# TerminalShield.net
KiCad netlist of a schematic drawn in EAGLE
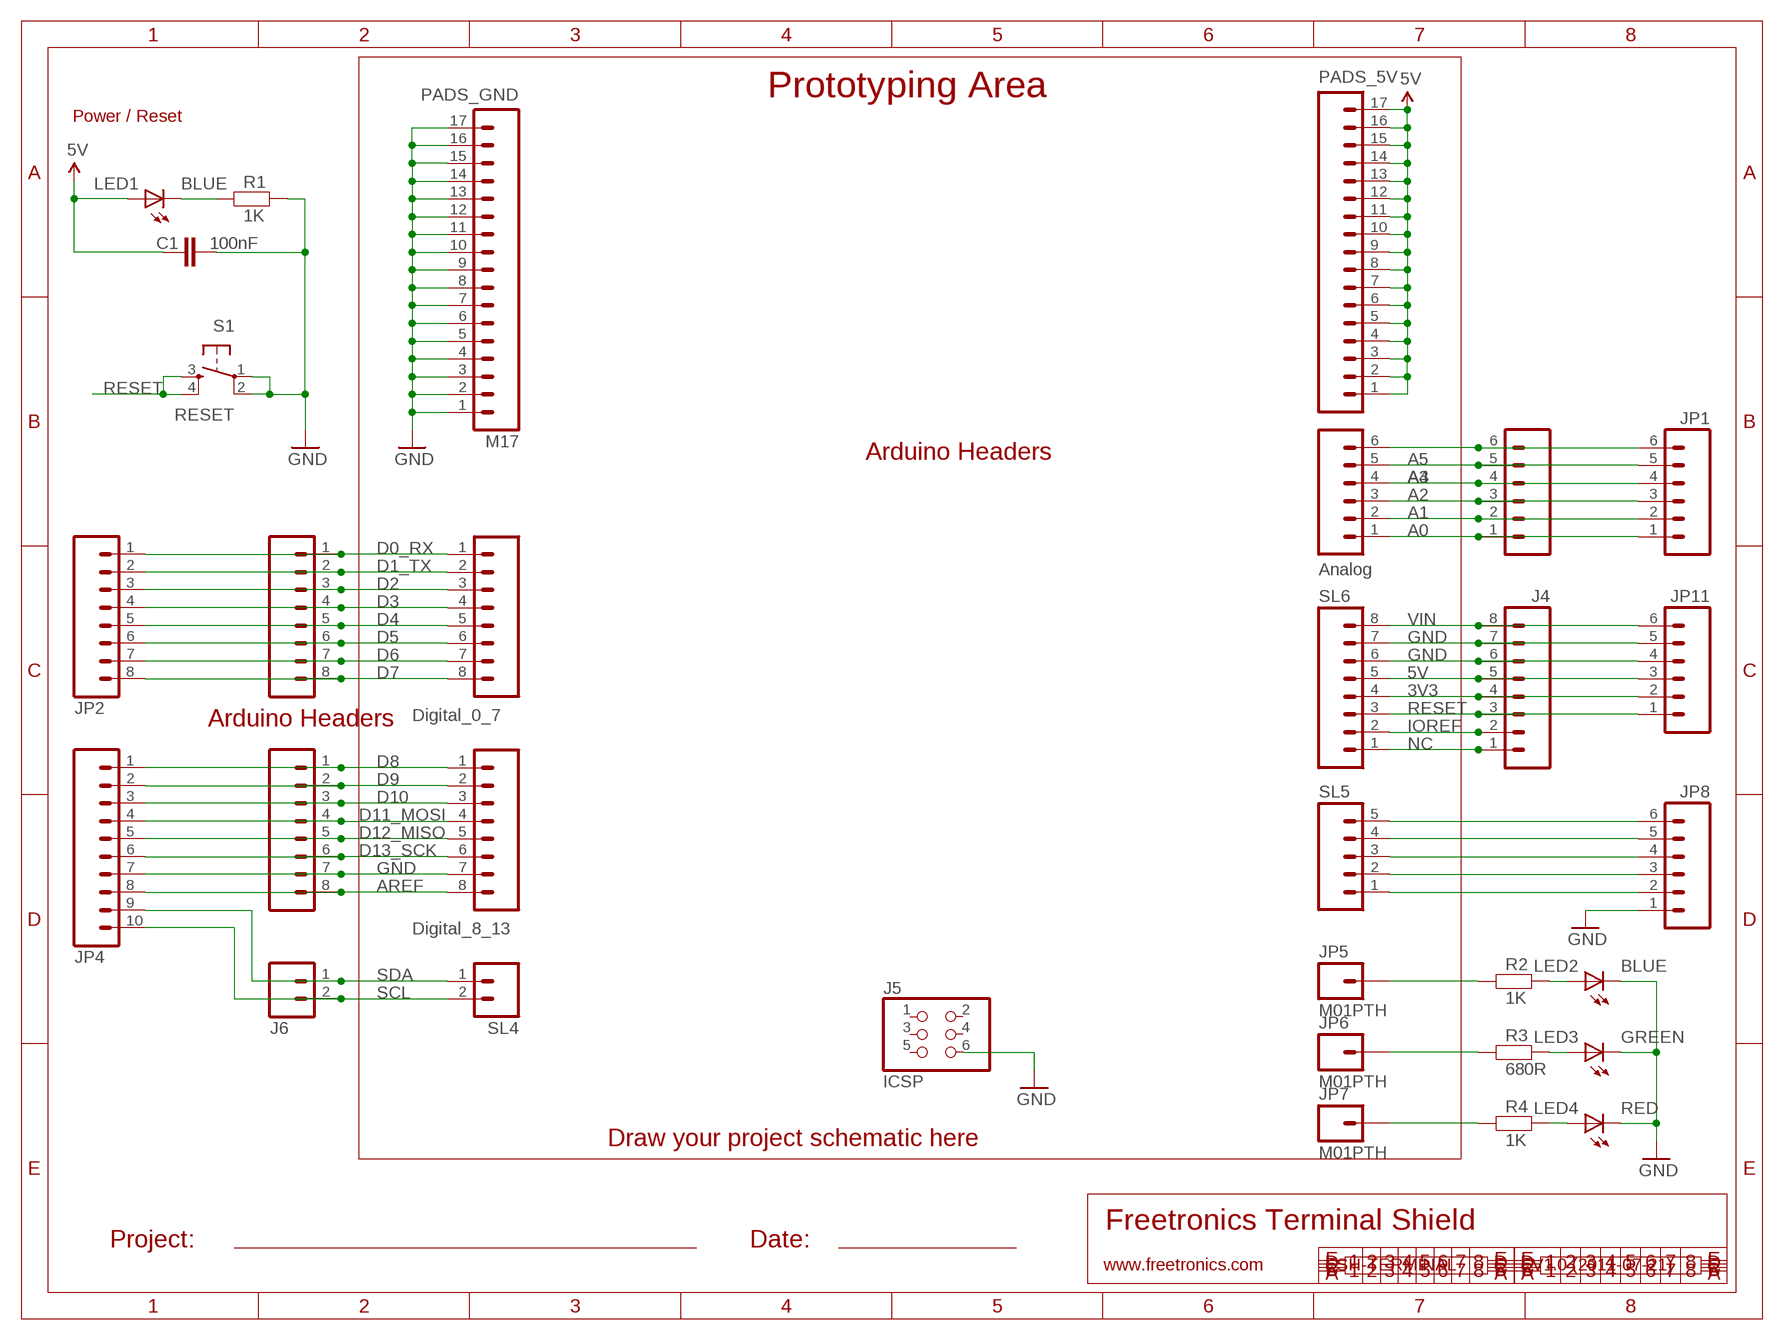
[diagram p0: schematic, sheet 1]

(export (version "E")
  (design (tool "Eeschema 10.0.6"))
  (components
    (comp (ref "C1")
      (value "100nF")
      (footprint "eagle-import:0603")
      (libsource (lib "eagle-import") (part "CAP0603"))
    )
    (comp (ref "J1")
      (value "Analog")
      (footprint "eagle-import:1X06")
      (libsource (lib "eagle-import") (part "M06SIP"))
    )
    (comp (ref "J2")
      (value "Digital_0_7")
      (footprint "eagle-import:1X08")
      (libsource (lib "eagle-import") (part "M08"))
    )
    (comp (ref "J3")
      (value "Digital_8_13")
      (footprint "eagle-import:1X08")
      (libsource (lib "eagle-import") (part "M08"))
    )
    (comp (ref "J4")
      (value "M08STD")
      (footprint "eagle-import:1X08")
      (libsource (lib "eagle-import") (part "M08STD"))
    )
    (comp (ref "J5")
      (value "ICSP")
      (footprint "eagle-import:2X03")
      (libsource (lib "eagle-import") (part "PINHD-2X3"))
    )
    (comp (ref "J6")
      (value "M02PTH")
      (footprint "eagle-import:1X02")
      (libsource (lib "eagle-import") (part "M02PTH"))
    )
    (comp (ref "JP1")
      (value "M06")
      (footprint "eagle-import:TERMINALBLOCK_3.5MM_6")
      (libsource (lib "eagle-import") (part "freetronics-master-v1_M06"))
    )
    (comp (ref "JP2")
      (value "M08")
      (footprint "eagle-import:TERMINALBLOCK_3.5MM_8")
      (libsource (lib "eagle-import") (part "freetronics-master-v1_M08"))
    )
    (comp (ref "JP4")
      (value "M10")
      (footprint "eagle-import:TERMINALBLOCK_3.5MM_10")
      (libsource (lib "eagle-import") (part "M10"))
    )
    (comp (ref "JP5")
      (value "M01PTH")
      (footprint "eagle-import:1X01")
      (libsource (lib "eagle-import") (part "M01PTH"))
    )
    (comp (ref "JP6")
      (value "M01PTH")
      (footprint "eagle-import:1X01")
      (libsource (lib "eagle-import") (part "M01PTH"))
    )
    (comp (ref "JP7")
      (value "M01PTH")
      (footprint "eagle-import:1X01")
      (libsource (lib "eagle-import") (part "M01PTH"))
    )
    (comp (ref "JP8")
      (value "M06")
      (footprint "eagle-import:TERMINALBLOCK_3.5MM_6")
      (libsource (lib "eagle-import") (part "M06"))
    )
    (comp (ref "JP11")
      (value "M06")
      (footprint "eagle-import:TERMINALBLOCK_3.5MM_6")
      (libsource (lib "eagle-import") (part "M06"))
    )
    (comp (ref "LED1")
      (value "BLUE")
      (footprint "eagle-import:LED-0603")
      (libsource (lib "eagle-import") (part "LED0603"))
    )
    (comp (ref "LED2")
      (value "BLUE")
      (footprint "eagle-import:LED-0603")
      (libsource (lib "eagle-import") (part "LED0603"))
    )
    (comp (ref "LED3")
      (value "GREEN")
      (footprint "eagle-import:LED-0603")
      (libsource (lib "eagle-import") (part "LED0603"))
    )
    (comp (ref "LED4")
      (value "RED")
      (footprint "eagle-import:LED-0603")
      (libsource (lib "eagle-import") (part "LED0603"))
    )
    (comp (ref "PADS_5V")
      (value "M17")
      (footprint "eagle-import:1X17")
      (libsource (lib "eagle-import") (part "M17"))
    )
    (comp (ref "PADS_GND")
      (value "M17")
      (footprint "eagle-import:1X17")
      (libsource (lib "eagle-import") (part "freetronics-master-v1.1_M17"))
    )
    (comp (ref "R1")
      (value "1K")
      (footprint "eagle-import:0603")
      (libsource (lib "eagle-import") (part "RESISTOR0603"))
    )
    (comp (ref "R2")
      (value "1K")
      (footprint "eagle-import:0603")
      (libsource (lib "eagle-import") (part "RESISTOR0603"))
    )
    (comp (ref "R3")
      (value "680R")
      (footprint "eagle-import:0603")
      (libsource (lib "eagle-import") (part "RESISTOR0603"))
    )
    (comp (ref "R4")
      (value "1K")
      (footprint "eagle-import:0603")
      (libsource (lib "eagle-import") (part "RESISTOR0603"))
    )
    (comp (ref "S1")
      (value "RESET")
      (footprint "eagle-import:TACTILE_SWITCH_SMD")
      (libsource (lib "eagle-import") (part "TAC_SWITCHSMD"))
    )
    (comp (ref "SL1")
      (value "Analog")
      (footprint "eagle-import:1X06")
      (libsource (lib "eagle-import") (part "M06SIP"))
    )
    (comp (ref "SL2")
      (value "Digital_0_7")
      (footprint "eagle-import:1X08")
      (libsource (lib "eagle-import") (part "M08"))
    )
    (comp (ref "SL3")
      (value "Digital_8_13")
      (footprint "eagle-import:1X08")
      (libsource (lib "eagle-import") (part "M08"))
    )
    (comp (ref "SL4")
      (value "M02PTH")
      (footprint "eagle-import:1X02")
      (libsource (lib "eagle-import") (part "M02PTH"))
    )
    (comp (ref "SL5")
      (value "M05PTH")
      (footprint "eagle-import:1X05")
      (libsource (lib "eagle-import") (part "M05PTH"))
    )
    (comp (ref "SL6")
      (value "M08STD")
      (footprint "eagle-import:1X08")
      (libsource (lib "eagle-import") (part "M08STD"))
    )
  )
  (nets
    (net (code "1") (name "/3V3") (class "Default")
      (node (ref "J4") (pin "4") (pinfunction "4_4") (pintype "passive"))
      (node (ref "JP11") (pin "2") (pinfunction "2_2") (pintype "passive"))
      (node (ref "SL6") (pin "4") (pinfunction "4_4") (pintype "passive"))
    )
    (net (code "2") (name "/A0") (class "Default")
      (node (ref "J1") (pin "1") (pinfunction "1_1") (pintype "passive"))
      (node (ref "JP1") (pin "1") (pinfunction "1_1") (pintype "passive"))
      (node (ref "SL1") (pin "1") (pinfunction "1_1") (pintype "passive"))
    )
    (net (code "3") (name "/A1") (class "Default")
      (node (ref "J1") (pin "2") (pinfunction "2_2") (pintype "passive"))
      (node (ref "JP1") (pin "2") (pinfunction "2_2") (pintype "passive"))
      (node (ref "SL1") (pin "2") (pinfunction "2_2") (pintype "passive"))
    )
    (net (code "4") (name "/A2") (class "Default")
      (node (ref "J1") (pin "3") (pinfunction "3_3") (pintype "passive"))
      (node (ref "JP1") (pin "3") (pinfunction "3_3") (pintype "passive"))
      (node (ref "SL1") (pin "3") (pinfunction "3_3") (pintype "passive"))
    )
    (net (code "5") (name "/A3") (class "Default")
      (node (ref "J1") (pin "4") (pinfunction "4_4") (pintype "passive"))
      (node (ref "JP1") (pin "4") (pinfunction "4_4") (pintype "passive"))
      (node (ref "SL1") (pin "4") (pinfunction "4_4") (pintype "passive"))
    )
    (net (code "6") (name "/A4") (class "Default")
      (node (ref "J1") (pin "5") (pinfunction "5_5") (pintype "passive"))
      (node (ref "JP1") (pin "5") (pinfunction "5_5") (pintype "passive"))
      (node (ref "SL1") (pin "5") (pinfunction "5_5") (pintype "passive"))
    )
    (net (code "7") (name "/A5") (class "Default")
      (node (ref "J1") (pin "6") (pinfunction "6_6") (pintype "passive"))
      (node (ref "JP1") (pin "6") (pinfunction "6_6") (pintype "passive"))
      (node (ref "SL1") (pin "6") (pinfunction "6_6") (pintype "passive"))
    )
    (net (code "8") (name "/AREF") (class "Default")
      (node (ref "J3") (pin "8") (pinfunction "8_8") (pintype "passive"))
      (node (ref "JP4") (pin "8") (pinfunction "8_8") (pintype "passive"))
      (node (ref "SL3") (pin "8") (pinfunction "8_8") (pintype "passive"))
    )
    (net (code "9") (name "/D0_RX") (class "Default")
      (node (ref "J2") (pin "1") (pinfunction "1_1") (pintype "passive"))
      (node (ref "JP2") (pin "1") (pinfunction "1_1") (pintype "passive"))
      (node (ref "SL2") (pin "1") (pinfunction "1_1") (pintype "passive"))
    )
    (net (code "10") (name "/D1_TX") (class "Default")
      (node (ref "J2") (pin "2") (pinfunction "2_2") (pintype "passive"))
      (node (ref "JP2") (pin "2") (pinfunction "2_2") (pintype "passive"))
      (node (ref "SL2") (pin "2") (pinfunction "2_2") (pintype "passive"))
    )
    (net (code "11") (name "/D2") (class "Default")
      (node (ref "J2") (pin "3") (pinfunction "3_3") (pintype "passive"))
      (node (ref "JP2") (pin "3") (pinfunction "3_3") (pintype "passive"))
      (node (ref "SL2") (pin "3") (pinfunction "3_3") (pintype "passive"))
    )
    (net (code "12") (name "/D3") (class "Default")
      (node (ref "J2") (pin "4") (pinfunction "4_4") (pintype "passive"))
      (node (ref "JP2") (pin "4") (pinfunction "4_4") (pintype "passive"))
      (node (ref "SL2") (pin "4") (pinfunction "4_4") (pintype "passive"))
    )
    (net (code "13") (name "/D4") (class "Default")
      (node (ref "J2") (pin "5") (pinfunction "5_5") (pintype "passive"))
      (node (ref "JP2") (pin "5") (pinfunction "5_5") (pintype "passive"))
      (node (ref "SL2") (pin "5") (pinfunction "5_5") (pintype "passive"))
    )
    (net (code "14") (name "/D5") (class "Default")
      (node (ref "J2") (pin "6") (pinfunction "6_6") (pintype "passive"))
      (node (ref "JP2") (pin "6") (pinfunction "6_6") (pintype "passive"))
      (node (ref "SL2") (pin "6") (pinfunction "6_6") (pintype "passive"))
    )
    (net (code "15") (name "/D6") (class "Default")
      (node (ref "J2") (pin "7") (pinfunction "7_7") (pintype "passive"))
      (node (ref "JP2") (pin "7") (pinfunction "7_7") (pintype "passive"))
      (node (ref "SL2") (pin "7") (pinfunction "7_7") (pintype "passive"))
    )
    (net (code "16") (name "/D7") (class "Default")
      (node (ref "J2") (pin "8") (pinfunction "8_8") (pintype "passive"))
      (node (ref "JP2") (pin "8") (pinfunction "8_8") (pintype "passive"))
      (node (ref "SL2") (pin "8") (pinfunction "8_8") (pintype "passive"))
    )
    (net (code "17") (name "/D8") (class "Default")
      (node (ref "J3") (pin "1") (pinfunction "1_1") (pintype "passive"))
      (node (ref "JP4") (pin "1") (pinfunction "1_1") (pintype "passive"))
      (node (ref "SL3") (pin "1") (pinfunction "1_1") (pintype "passive"))
    )
    (net (code "18") (name "/D9") (class "Default")
      (node (ref "J3") (pin "2") (pinfunction "2_2") (pintype "passive"))
      (node (ref "JP4") (pin "2") (pinfunction "2_2") (pintype "passive"))
      (node (ref "SL3") (pin "2") (pinfunction "2_2") (pintype "passive"))
    )
    (net (code "19") (name "/D10") (class "Default")
      (node (ref "J3") (pin "3") (pinfunction "3_3") (pintype "passive"))
      (node (ref "JP4") (pin "3") (pinfunction "3_3") (pintype "passive"))
      (node (ref "SL3") (pin "3") (pinfunction "3_3") (pintype "passive"))
    )
    (net (code "20") (name "/D11_MOSI") (class "Default")
      (node (ref "J3") (pin "4") (pinfunction "4_4") (pintype "passive"))
      (node (ref "JP4") (pin "4") (pinfunction "4_4") (pintype "passive"))
      (node (ref "SL3") (pin "4") (pinfunction "4_4") (pintype "passive"))
    )
    (net (code "21") (name "/D12_MISO") (class "Default")
      (node (ref "J3") (pin "5") (pinfunction "5_5") (pintype "passive"))
      (node (ref "JP4") (pin "5") (pinfunction "5_5") (pintype "passive"))
      (node (ref "SL3") (pin "5") (pinfunction "5_5") (pintype "passive"))
    )
    (net (code "22") (name "/D13_SCK") (class "Default")
      (node (ref "J3") (pin "6") (pinfunction "6_6") (pintype "passive"))
      (node (ref "JP4") (pin "6") (pinfunction "6_6") (pintype "passive"))
      (node (ref "SL3") (pin "6") (pinfunction "6_6") (pintype "passive"))
    )
    (net (code "23") (name "/IOREF") (class "Default")
      (node (ref "J4") (pin "2") (pinfunction "2_2") (pintype "passive"))
      (node (ref "SL6") (pin "2") (pinfunction "2_2") (pintype "passive"))
    )
    (net (code "24") (name "/NC") (class "Default")
      (node (ref "J4") (pin "1") (pinfunction "1_1") (pintype "passive"))
      (node (ref "SL6") (pin "1") (pinfunction "1_1") (pintype "passive"))
    )
    (net (code "25") (name "/RESET") (class "Default")
      (node (ref "J4") (pin "3") (pinfunction "3_3") (pintype "passive"))
      (node (ref "JP11") (pin "1") (pinfunction "1_1") (pintype "passive"))
      (node (ref "S1") (pin "3") (pinfunction "3_3") (pintype "passive"))
      (node (ref "S1") (pin "4") (pinfunction "4_4") (pintype "passive"))
      (node (ref "SL6") (pin "3") (pinfunction "3_3") (pintype "passive"))
    )
    (net (code "26") (name "/SCL") (class "Default")
      (node (ref "J6") (pin "2") (pinfunction "2_2") (pintype "passive"))
      (node (ref "JP4") (pin "10") (pinfunction "10_10") (pintype "passive"))
      (node (ref "SL4") (pin "2") (pinfunction "2_2") (pintype "passive"))
    )
    (net (code "27") (name "/SDA") (class "Default")
      (node (ref "J6") (pin "1") (pinfunction "1_1") (pintype "passive"))
      (node (ref "JP4") (pin "9") (pinfunction "9_9") (pintype "passive"))
      (node (ref "SL4") (pin "1") (pinfunction "1_1") (pintype "passive"))
    )
    (net (code "28") (name "/VIN") (class "Default")
      (node (ref "J4") (pin "8") (pinfunction "8_8") (pintype "passive"))
      (node (ref "JP11") (pin "6") (pinfunction "6_6") (pintype "passive"))
      (node (ref "SL6") (pin "8") (pinfunction "8_8") (pintype "passive"))
    )
    (net (code "29") (name "5V") (class "Default")
      (node (ref "C1") (pin "1") (pinfunction "1_1") (pintype "passive"))
      (node (ref "J4") (pin "5") (pinfunction "5_5") (pintype "passive"))
      (node (ref "JP11") (pin "3") (pinfunction "3_3") (pintype "passive"))
      (node (ref "LED1") (pin "A") (pinfunction "A_A") (pintype "passive"))
      (node (ref "PADS_5V") (pin "1") (pinfunction "1_1") (pintype "passive"))
      (node (ref "PADS_5V") (pin "10") (pinfunction "10_10") (pintype "passive"))
      (node (ref "PADS_5V") (pin "11") (pinfunction "11_11") (pintype "passive"))
      (node (ref "PADS_5V") (pin "12") (pinfunction "12_12") (pintype "passive"))
      (node (ref "PADS_5V") (pin "13") (pinfunction "13_13") (pintype "passive"))
      (node (ref "PADS_5V") (pin "14") (pinfunction "14_14") (pintype "passive"))
      (node (ref "PADS_5V") (pin "15") (pinfunction "15_15") (pintype "passive"))
      (node (ref "PADS_5V") (pin "16") (pinfunction "16_16") (pintype "passive"))
      (node (ref "PADS_5V") (pin "17") (pinfunction "17_17") (pintype "passive"))
      (node (ref "PADS_5V") (pin "2") (pinfunction "2_2") (pintype "passive"))
      (node (ref "PADS_5V") (pin "3") (pinfunction "3_3") (pintype "passive"))
      (node (ref "PADS_5V") (pin "4") (pinfunction "4_4") (pintype "passive"))
      (node (ref "PADS_5V") (pin "5") (pinfunction "5_5") (pintype "passive"))
      (node (ref "PADS_5V") (pin "6") (pinfunction "6_6") (pintype "passive"))
      (node (ref "PADS_5V") (pin "7") (pinfunction "7_7") (pintype "passive"))
      (node (ref "PADS_5V") (pin "8") (pinfunction "8_8") (pintype "passive"))
      (node (ref "PADS_5V") (pin "9") (pinfunction "9_9") (pintype "passive"))
      (node (ref "SL6") (pin "5") (pinfunction "5_5") (pintype "passive"))
    )
    (net (code "30") (name "GND") (class "Default")
      (node (ref "C1") (pin "2") (pinfunction "2_2") (pintype "passive"))
      (node (ref "J3") (pin "7") (pinfunction "7_7") (pintype "passive"))
      (node (ref "J4") (pin "6") (pinfunction "6_6") (pintype "passive"))
      (node (ref "J4") (pin "7") (pinfunction "7_7") (pintype "passive"))
      (node (ref "J5") (pin "6") (pinfunction "6_6") (pintype "passive"))
      (node (ref "JP11") (pin "4") (pinfunction "4_4") (pintype "passive"))
      (node (ref "JP11") (pin "5") (pinfunction "5_5") (pintype "passive"))
      (node (ref "JP4") (pin "7") (pinfunction "7_7") (pintype "passive"))
      (node (ref "JP8") (pin "1") (pinfunction "1_1") (pintype "passive"))
      (node (ref "LED2") (pin "C") (pinfunction "C_C") (pintype "passive"))
      (node (ref "LED3") (pin "C") (pinfunction "C_C") (pintype "passive"))
      (node (ref "LED4") (pin "C") (pinfunction "C_C") (pintype "passive"))
      (node (ref "PADS_GND") (pin "1") (pinfunction "1_1") (pintype "passive"))
      (node (ref "PADS_GND") (pin "10") (pinfunction "10_10") (pintype "passive"))
      (node (ref "PADS_GND") (pin "11") (pinfunction "11_11") (pintype "passive"))
      (node (ref "PADS_GND") (pin "12") (pinfunction "12_12") (pintype "passive"))
      (node (ref "PADS_GND") (pin "13") (pinfunction "13_13") (pintype "passive"))
      (node (ref "PADS_GND") (pin "14") (pinfunction "14_14") (pintype "passive"))
      (node (ref "PADS_GND") (pin "15") (pinfunction "15_15") (pintype "passive"))
      (node (ref "PADS_GND") (pin "16") (pinfunction "16_16") (pintype "passive"))
      (node (ref "PADS_GND") (pin "17") (pinfunction "17_17") (pintype "passive"))
      (node (ref "PADS_GND") (pin "2") (pinfunction "2_2") (pintype "passive"))
      (node (ref "PADS_GND") (pin "3") (pinfunction "3_3") (pintype "passive"))
      (node (ref "PADS_GND") (pin "4") (pinfunction "4_4") (pintype "passive"))
      (node (ref "PADS_GND") (pin "5") (pinfunction "5_5") (pintype "passive"))
      (node (ref "PADS_GND") (pin "6") (pinfunction "6_6") (pintype "passive"))
      (node (ref "PADS_GND") (pin "7") (pinfunction "7_7") (pintype "passive"))
      (node (ref "PADS_GND") (pin "8") (pinfunction "8_8") (pintype "passive"))
      (node (ref "PADS_GND") (pin "9") (pinfunction "9_9") (pintype "passive"))
      (node (ref "R1") (pin "2") (pinfunction "2_2") (pintype "passive"))
      (node (ref "S1") (pin "1") (pinfunction "1_1") (pintype "passive"))
      (node (ref "S1") (pin "2") (pinfunction "2_2") (pintype "passive"))
      (node (ref "SL3") (pin "7") (pinfunction "7_7") (pintype "passive"))
      (node (ref "SL6") (pin "6") (pinfunction "6_6") (pintype "passive"))
      (node (ref "SL6") (pin "7") (pinfunction "7_7") (pintype "passive"))
    )
    (net (code "31") (name "Net-(JP5-Pad1)") (class "Default")
      (node (ref "JP5") (pin "1") (pinfunction "1_1") (pintype "passive"))
      (node (ref "R2") (pin "1") (pinfunction "1_1") (pintype "passive"))
    )
    (net (code "32") (name "Net-(JP6-Pad1)") (class "Default")
      (node (ref "JP6") (pin "1") (pinfunction "1_1") (pintype "passive"))
      (node (ref "R3") (pin "1") (pinfunction "1_1") (pintype "passive"))
    )
    (net (code "33") (name "Net-(JP7-Pad1)") (class "Default")
      (node (ref "JP7") (pin "1") (pinfunction "1_1") (pintype "passive"))
      (node (ref "R4") (pin "1") (pinfunction "1_1") (pintype "passive"))
    )
    (net (code "34") (name "Net-(JP8-Pad2)") (class "Default")
      (node (ref "JP8") (pin "2") (pinfunction "2_2") (pintype "passive"))
      (node (ref "SL5") (pin "1") (pinfunction "1_1") (pintype "passive"))
    )
    (net (code "35") (name "Net-(JP8-Pad3)") (class "Default")
      (node (ref "JP8") (pin "3") (pinfunction "3_3") (pintype "passive"))
      (node (ref "SL5") (pin "2") (pinfunction "2_2") (pintype "passive"))
    )
    (net (code "36") (name "Net-(JP8-Pad4)") (class "Default")
      (node (ref "JP8") (pin "4") (pinfunction "4_4") (pintype "passive"))
      (node (ref "SL5") (pin "3") (pinfunction "3_3") (pintype "passive"))
    )
    (net (code "37") (name "Net-(JP8-Pad5)") (class "Default")
      (node (ref "JP8") (pin "5") (pinfunction "5_5") (pintype "passive"))
      (node (ref "SL5") (pin "4") (pinfunction "4_4") (pintype "passive"))
    )
    (net (code "38") (name "Net-(JP8-Pad6)") (class "Default")
      (node (ref "JP8") (pin "6") (pinfunction "6_6") (pintype "passive"))
      (node (ref "SL5") (pin "5") (pinfunction "5_5") (pintype "passive"))
    )
    (net (code "39") (name "Net-(LED1-PadC)") (class "Default")
      (node (ref "LED1") (pin "C") (pinfunction "C_C") (pintype "passive"))
      (node (ref "R1") (pin "1") (pinfunction "1_1") (pintype "passive"))
    )
    (net (code "40") (name "Net-(LED2-PadA)") (class "Default")
      (node (ref "LED2") (pin "A") (pinfunction "A_A") (pintype "passive"))
      (node (ref "R2") (pin "2") (pinfunction "2_2") (pintype "passive"))
    )
    (net (code "41") (name "Net-(LED3-PadA)") (class "Default")
      (node (ref "LED3") (pin "A") (pinfunction "A_A") (pintype "passive"))
      (node (ref "R3") (pin "2") (pinfunction "2_2") (pintype "passive"))
    )
    (net (code "42") (name "Net-(LED4-PadA)") (class "Default")
      (node (ref "LED4") (pin "A") (pinfunction "A_A") (pintype "passive"))
      (node (ref "R4") (pin "2") (pinfunction "2_2") (pintype "passive"))
    )
    (net (code "43") (name "unconnected-(J5-Pad1)") (class "Default")
      (node (ref "J5") (pin "1") (pinfunction "1_1") (pintype "passive"))
    )
    (net (code "44") (name "unconnected-(J5-Pad2)") (class "Default")
      (node (ref "J5") (pin "2") (pinfunction "2_2") (pintype "passive"))
    )
    (net (code "45") (name "unconnected-(J5-Pad3)") (class "Default")
      (node (ref "J5") (pin "3") (pinfunction "3_3") (pintype "passive"))
    )
    (net (code "46") (name "unconnected-(J5-Pad4)") (class "Default")
      (node (ref "J5") (pin "4") (pinfunction "4_4") (pintype "passive"))
    )
    (net (code "47") (name "unconnected-(J5-Pad5)") (class "Default")
      (node (ref "J5") (pin "5") (pinfunction "5_5") (pintype "passive"))
    )
  )
)
